# PowerSupply.net
KiCad netlist of a schematic drawn in Altium Designer
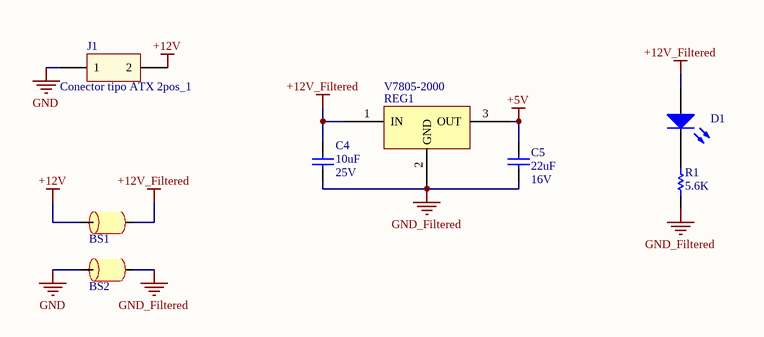
[diagram p0: PowerSupply.SchDoc]

(export (version "E")
  (design (tool "Eeschema 10.0.6"))
  (components
    (comp (ref "BS1")
      (value "Ferrite bead")
      (footprint "RES_1206")
      (description "4A")
      (libsource (lib "Componentes_SOC") (part "Bead"))
    )
    (comp (ref "BS2")
      (value "Ferrite bead")
      (footprint "RES_1206")
      (description "4A")
      (libsource (lib "Componentes_SOC") (part "Bead"))
    )
    (comp (ref "C4")
      (value "10uF")
      (footprint "CAP_0603")
      (description "Capacitor Ceramic")
      (fields (field (name "VOLTAGE") "25V"))
      (libsource (lib "Componentes_SOC") (part "Cap_0603"))
    )
    (comp (ref "C5")
      (value "22uF")
      (footprint "CAP_0805")
      (description "Capacitor")
      (fields (field (name "VOLTAGE") "16V"))
      (libsource (lib "Componentes_SOC") (part "Cap_0805"))
    )
    (comp (ref "D1")
      (value "LED")
      (footprint "LED_0805_GREEN")
      (description "LED Magenta")
      (fields (field (name "PUBLISHER") "Altium Limited"))
      (libsource (lib "Componentes_SOC") (part "LED2"))
    )
    (comp (ref "J1")
      (value "Conector tipo ATX 2pos_1")
      (footprint "Conector tipo ATX Wurth 2 posiciones - (5.5mm)")
      (description "CONN HEADER VERT 2POS 5.5MM")
      (libsource (lib "Componentes_SOC") (part "Conector tipo ATX 2pos_1"))
    )
    (comp (ref "R1")
      (value "5.6K")
      (footprint "RES_0805")
      (fields (field (name "PUBLISHER") "Altium Limited"))
      (libsource (lib "Componentes_SOC") (part "Res0805"))
    )
    (comp (ref "REG1")
      (value "V7805-2000")
      (footprint "REG_SW 5V")
      (description "DC/DC Converter")
      (libsource (lib "Componentes_SOC") (part "V78XX"))
    )
  )
  (nets
    (net (code "1") (name "+5V") (class "Default")
      (node (ref "C5") (pin "1") (pinfunction "1_1") (pintype "passive"))
      (node (ref "REG1") (pin "3") (pinfunction "OUT_3") (pintype "passive"))
    )
    (net (code "2") (name "+12V") (class "Default")
      (node (ref "BS1") (pin "1") (pintype "passive"))
      (node (ref "J1") (pin "2") (pinfunction "2_2") (pintype "passive"))
    )
    (net (code "3") (name "+12V_Filtered") (class "Default")
      (node (ref "BS1") (pin "2") (pintype "passive"))
      (node (ref "C4") (pin "1") (pinfunction "1_1") (pintype "passive"))
      (node (ref "D1") (pin "1") (pinfunction "A_1") (pintype "passive"))
      (node (ref "REG1") (pin "1") (pinfunction "IN_1") (pintype "passive"))
    )
    (net (code "4") (name "GND") (class "Default")
      (node (ref "BS2") (pin "1") (pintype "passive"))
      (node (ref "J1") (pin "1") (pinfunction "1_1") (pintype "passive"))
    )
    (net (code "5") (name "GND_Filtered") (class "Default")
      (node (ref "BS2") (pin "2") (pintype "passive"))
      (node (ref "C4") (pin "2") (pinfunction "2_2") (pintype "passive"))
      (node (ref "C5") (pin "2") (pinfunction "2_2") (pintype "passive"))
      (node (ref "R1") (pin "1") (pinfunction "1_1") (pintype "passive"))
      (node (ref "REG1") (pin "2") (pinfunction "GND_2") (pintype "passive"))
    )
    (net (code "6") (name "Net-(D1-K)") (class "Default")
      (node (ref "D1") (pin "2") (pinfunction "K_2") (pintype "passive"))
      (node (ref "R1") (pin "2") (pinfunction "2_2") (pintype "passive"))
    )
  )
)
